# DAC.net
KiCad netlist of a schematic drawn in Altium Designer
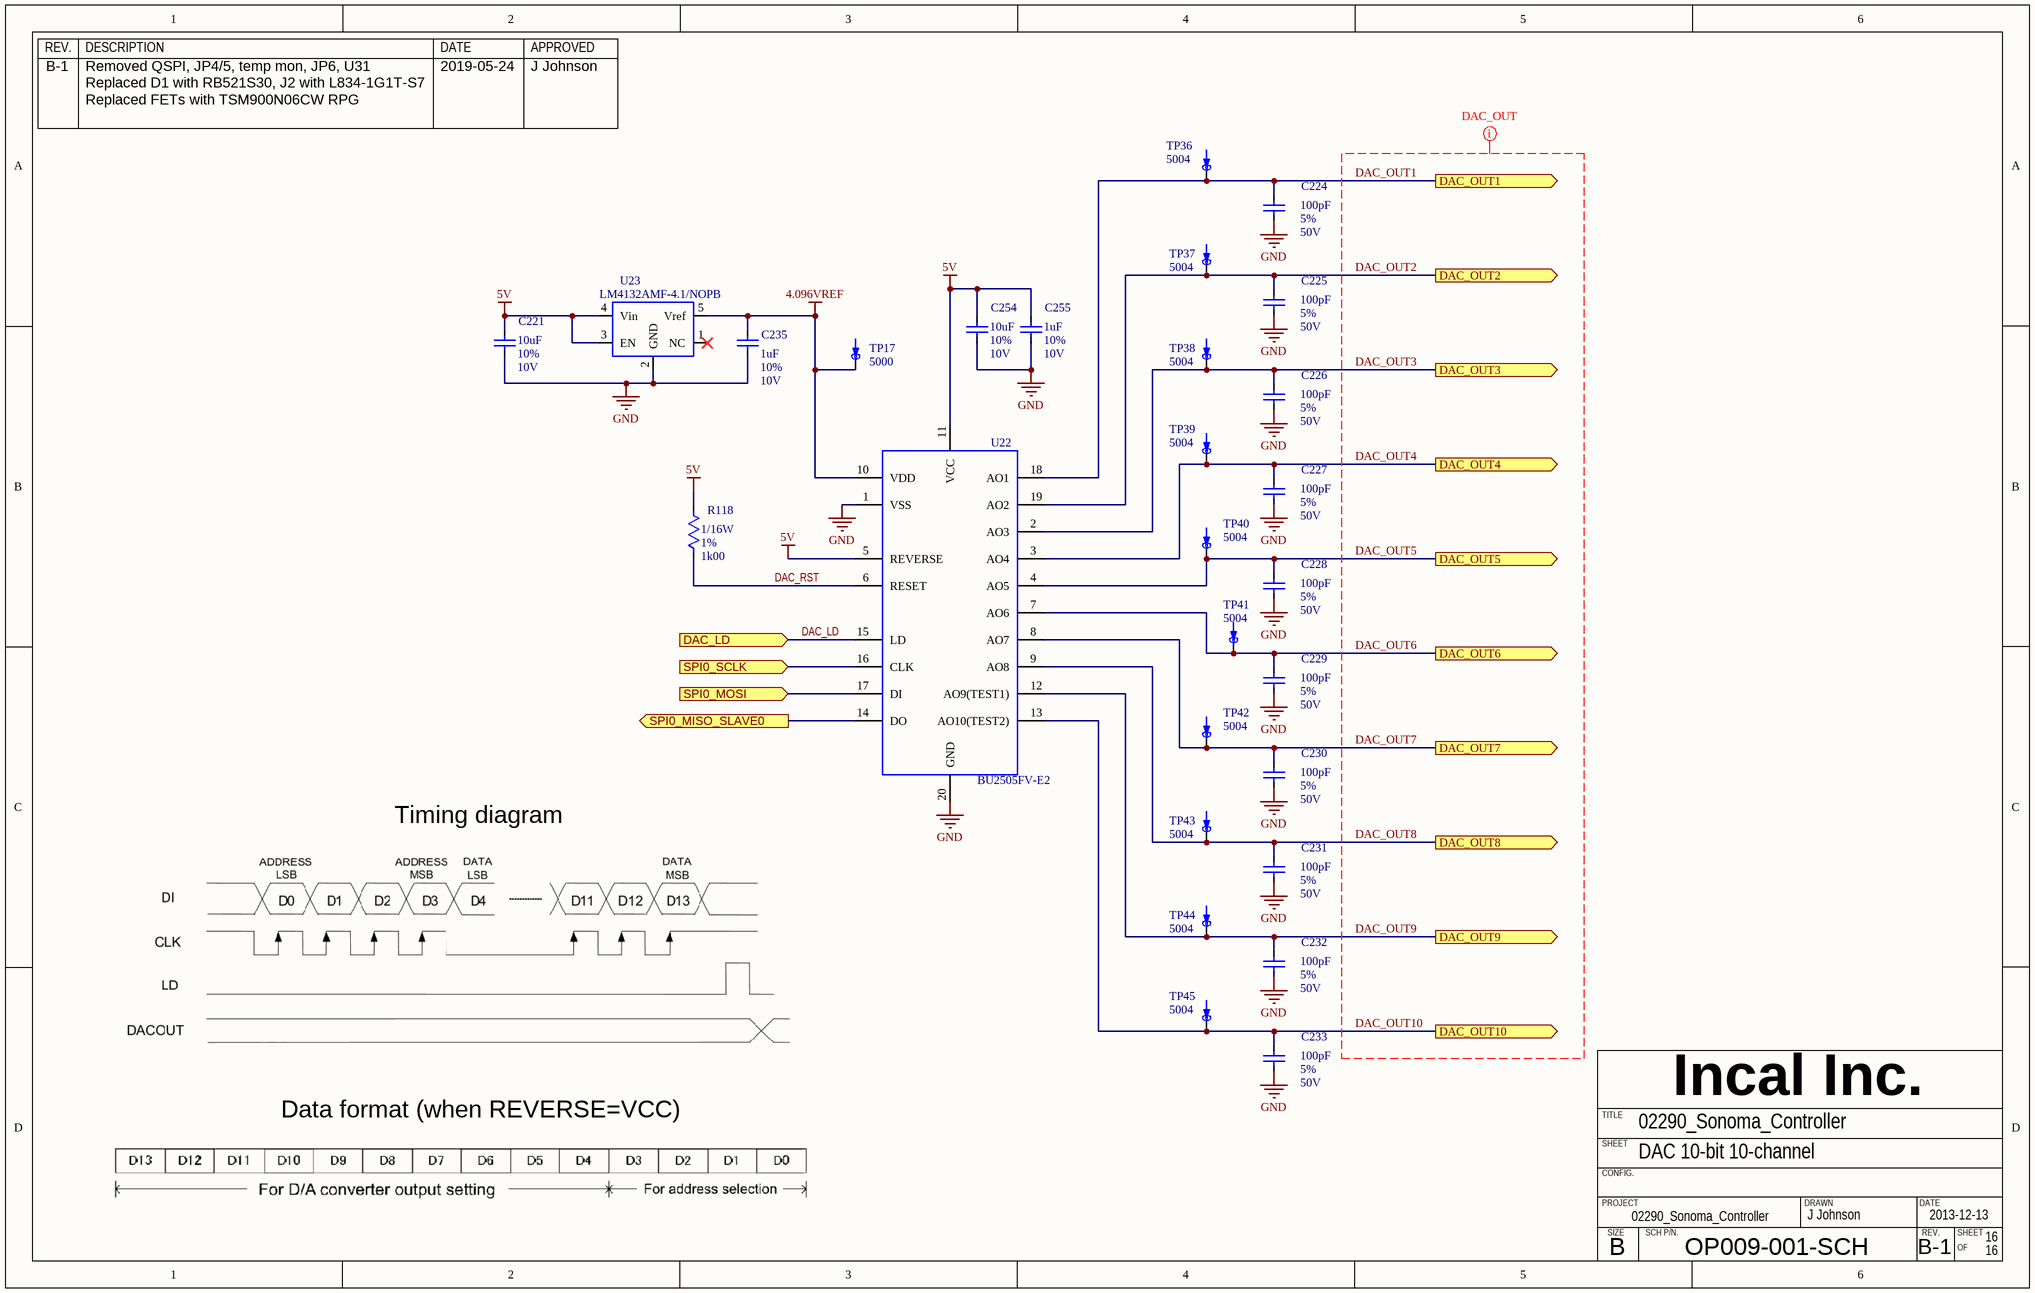
[diagram p0: DAC.SchDoc]

(export (version "E")
  (design (tool "Eeschema 10.0.6"))
  (components
    (comp (ref "C221")
      (value "10uF")
      (footprint "CAPC1608X38N")
      (description "Capacitor ceramic, X5R, 10uF, 10V, 10%, -55 to +85 C, EIA0603")
      (fields
        (field (name "TOLERANCE") "10%")
        (field (name "VOLTAGE") "10V")
        (field (name "Comment") "CAPACITOR_NP_TYPE1")
      )
      (libsource (lib "parts") (part "CAPACITOR_NP_TYPE1"))
    )
    (comp (ref "C224")
      (value "100pF")
      (footprint "CAPC1005X33N")
      (description "Capacitor ceramic, C0G (NP0), 100pF, 50V, 5%, -55 to +125 C, EIA0402")
      (fields
        (field (name "TOLERANCE") "5%")
        (field (name "VOLTAGE") "50V")
        (field (name "Comment") "CAPACITOR_NP_TYPE1")
      )
      (libsource (lib "parts") (part "CAPACITOR_NP_TYPE1"))
    )
    (comp (ref "C225")
      (value "100pF")
      (footprint "CAPC1005X33N")
      (description "Capacitor ceramic, C0G (NP0), 100pF, 50V, 5%, -55 to +125 C, EIA0402")
      (fields
        (field (name "TOLERANCE") "5%")
        (field (name "VOLTAGE") "50V")
        (field (name "Comment") "CAPACITOR_NP_TYPE1")
      )
      (libsource (lib "parts") (part "CAPACITOR_NP_TYPE1"))
    )
    (comp (ref "C226")
      (value "100pF")
      (footprint "CAPC1005X33N")
      (description "Capacitor ceramic, C0G (NP0), 100pF, 50V, 5%, -55 to +125 C, EIA0402")
      (fields
        (field (name "TOLERANCE") "5%")
        (field (name "VOLTAGE") "50V")
        (field (name "Comment") "CAPACITOR_NP_TYPE1")
      )
      (libsource (lib "parts") (part "CAPACITOR_NP_TYPE1"))
    )
    (comp (ref "C227")
      (value "100pF")
      (footprint "CAPC1005X33N")
      (description "Capacitor ceramic, C0G (NP0), 100pF, 50V, 5%, -55 to +125 C, EIA0402")
      (fields
        (field (name "TOLERANCE") "5%")
        (field (name "VOLTAGE") "50V")
        (field (name "Comment") "CAPACITOR_NP_TYPE1")
      )
      (libsource (lib "parts") (part "CAPACITOR_NP_TYPE1"))
    )
    (comp (ref "C228")
      (value "100pF")
      (footprint "CAPC1005X33N")
      (description "Capacitor ceramic, C0G (NP0), 100pF, 50V, 5%, -55 to +125 C, EIA0402")
      (fields
        (field (name "TOLERANCE") "5%")
        (field (name "VOLTAGE") "50V")
        (field (name "Comment") "CAPACITOR_NP_TYPE1")
      )
      (libsource (lib "parts") (part "CAPACITOR_NP_TYPE1"))
    )
    (comp (ref "C229")
      (value "100pF")
      (footprint "CAPC1005X33N")
      (description "Capacitor ceramic, C0G (NP0), 100pF, 50V, 5%, -55 to +125 C, EIA0402")
      (fields
        (field (name "TOLERANCE") "5%")
        (field (name "VOLTAGE") "50V")
        (field (name "Comment") "CAPACITOR_NP_TYPE1")
      )
      (libsource (lib "parts") (part "CAPACITOR_NP_TYPE1"))
    )
    (comp (ref "C230")
      (value "100pF")
      (footprint "CAPC1005X33N")
      (description "Capacitor ceramic, C0G (NP0), 100pF, 50V, 5%, -55 to +125 C, EIA0402")
      (fields
        (field (name "TOLERANCE") "5%")
        (field (name "VOLTAGE") "50V")
        (field (name "Comment") "CAPACITOR_NP_TYPE1")
      )
      (libsource (lib "parts") (part "CAPACITOR_NP_TYPE1"))
    )
    (comp (ref "C231")
      (value "100pF")
      (footprint "CAPC1005X33N")
      (description "Capacitor ceramic, C0G (NP0), 100pF, 50V, 5%, -55 to +125 C, EIA0402")
      (fields
        (field (name "TOLERANCE") "5%")
        (field (name "VOLTAGE") "50V")
        (field (name "Comment") "CAPACITOR_NP_TYPE1")
      )
      (libsource (lib "parts") (part "CAPACITOR_NP_TYPE1"))
    )
    (comp (ref "C232")
      (value "100pF")
      (footprint "CAPC1005X33N")
      (description "Capacitor ceramic, C0G (NP0), 100pF, 50V, 5%, -55 to +125 C, EIA0402")
      (fields
        (field (name "TOLERANCE") "5%")
        (field (name "VOLTAGE") "50V")
        (field (name "Comment") "CAPACITOR_NP_TYPE1")
      )
      (libsource (lib "parts") (part "CAPACITOR_NP_TYPE1"))
    )
    (comp (ref "C233")
      (value "100pF")
      (footprint "CAPC1005X33N")
      (description "Capacitor ceramic, C0G (NP0), 100pF, 50V, 5%, -55 to +125 C, EIA0402")
      (fields
        (field (name "TOLERANCE") "5%")
        (field (name "VOLTAGE") "50V")
        (field (name "Comment") "CAPACITOR_NP_TYPE1")
      )
      (libsource (lib "parts") (part "CAPACITOR_NP_TYPE1"))
    )
    (comp (ref "C235")
      (value "1uF")
      (footprint "CAPC1005X33N")
      (description "Capacitor ceramic, X5R, 1uF, 10V, 10%, -55 to +85 C, EIA0402")
      (fields
        (field (name "TOLERANCE") "10%")
        (field (name "VOLTAGE") "10V")
        (field (name "Comment") "CAPACITOR_NP_TYPE1")
      )
      (libsource (lib "parts") (part "CAPACITOR_NP_TYPE1"))
    )
    (comp (ref "C254")
      (value "10uF")
      (footprint "CAPC1608X38N")
      (description "Capacitor ceramic, X5R, 10uF, 10V, 10%, -55 to +85 C, EIA0603")
      (fields
        (field (name "TOLERANCE") "10%")
        (field (name "VOLTAGE") "10V")
        (field (name "Comment") "CAPACITOR_NP_TYPE1")
      )
      (libsource (lib "parts") (part "CAPACITOR_NP_TYPE1"))
    )
    (comp (ref "C255")
      (value "1uF")
      (footprint "CAPC1005X33N")
      (description "Capacitor ceramic, X5R, 1uF, 10V, 10%, -55 to +85 C, EIA0402")
      (fields
        (field (name "TOLERANCE") "10%")
        (field (name "VOLTAGE") "10V")
        (field (name "Comment") "CAPACITOR_NP_TYPE1")
      )
      (libsource (lib "parts") (part "CAPACITOR_NP_TYPE1"))
    )
    (comp (ref "R118")
      (value "1k00")
      (footprint "RESC1005X33N")
      (description "Resistor, 1k00, 1/16W, 1%, -55 to +155 C, EIA0402")
      (fields (field (name "VOLTAGE") "50V") (field (name "POWER") "1/16W") (field (name "TOLERANCE") "1%"))
      (libsource (lib "parts") (part "RESISTOR_TYPE1"))
    )
    (comp (ref "TP17")
      (value "5000")
      (footprint "KEY_5000")
      (description "Test point bead, red, Keystone Electronics, Thru-hole,")
      (fields (field (name "POWER") "Pow") (field (name "VOLTAGE") "Vol"))
      (libsource (lib "parts") (part "TEST_POINT_TYPE4"))
    )
    (comp (ref "TP36")
      (value "5004")
      (footprint "KEY_5004")
      (description "Test point bead, yellow, Keystone Electronics, Thru-hole,")
      (fields (field (name "POWER") "Pow") (field (name "VOLTAGE") "Vol"))
      (libsource (lib "parts") (part "TEST_POINT_TYPE4"))
    )
    (comp (ref "TP37")
      (value "5004")
      (footprint "KEY_5004")
      (description "Test point bead, yellow, Keystone Electronics, Thru-hole,")
      (fields (field (name "POWER") "Pow") (field (name "VOLTAGE") "Vol"))
      (libsource (lib "parts") (part "TEST_POINT_TYPE4"))
    )
    (comp (ref "TP38")
      (value "5004")
      (footprint "KEY_5004")
      (description "Test point bead, yellow, Keystone Electronics, Thru-hole,")
      (fields (field (name "POWER") "Pow") (field (name "VOLTAGE") "Vol"))
      (libsource (lib "parts") (part "TEST_POINT_TYPE4"))
    )
    (comp (ref "TP39")
      (value "5004")
      (footprint "KEY_5004")
      (description "Test point bead, yellow, Keystone Electronics, Thru-hole,")
      (fields (field (name "POWER") "Pow") (field (name "VOLTAGE") "Vol"))
      (libsource (lib "parts") (part "TEST_POINT_TYPE4"))
    )
    (comp (ref "TP40")
      (value "5004")
      (footprint "KEY_5004")
      (description "Test point bead, yellow, Keystone Electronics, Thru-hole,")
      (fields (field (name "POWER") "Pow") (field (name "VOLTAGE") "Vol"))
      (libsource (lib "parts") (part "TEST_POINT_TYPE4"))
    )
    (comp (ref "TP41")
      (value "5004")
      (footprint "KEY_5004")
      (description "Test point bead, yellow, Keystone Electronics, Thru-hole,")
      (fields (field (name "POWER") "Pow") (field (name "VOLTAGE") "Vol"))
      (libsource (lib "parts") (part "TEST_POINT_TYPE4"))
    )
    (comp (ref "TP42")
      (value "5004")
      (footprint "KEY_5004")
      (description "Test point bead, yellow, Keystone Electronics, Thru-hole,")
      (fields (field (name "POWER") "Pow") (field (name "VOLTAGE") "Vol"))
      (libsource (lib "parts") (part "TEST_POINT_TYPE4"))
    )
    (comp (ref "TP43")
      (value "5004")
      (footprint "KEY_5004")
      (description "Test point bead, yellow, Keystone Electronics, Thru-hole,")
      (fields (field (name "POWER") "Pow") (field (name "VOLTAGE") "Vol"))
      (libsource (lib "parts") (part "TEST_POINT_TYPE4"))
    )
    (comp (ref "TP44")
      (value "5004")
      (footprint "KEY_5004")
      (description "Test point bead, yellow, Keystone Electronics, Thru-hole,")
      (fields (field (name "POWER") "Pow") (field (name "VOLTAGE") "Vol"))
      (libsource (lib "parts") (part "TEST_POINT_TYPE4"))
    )
    (comp (ref "TP45")
      (value "5004")
      (footprint "KEY_5004")
      (description "Test point bead, yellow, Keystone Electronics, Thru-hole,")
      (fields (field (name "POWER") "Pow") (field (name "VOLTAGE") "Vol"))
      (libsource (lib "parts") (part "TEST_POINT_TYPE4"))
    )
    (comp (ref "U22")
      (value "BU2505FV-E2")
      (footprint "SSOP65P440X650X115-20N")
      (description "DAC 10 bit, High precision, 10 channel, 4.5 to 5.5V, -30 to +85C")
      (libsource (lib "parts") (part "BU2505FV-E2"))
    )
    (comp (ref "U23")
      (value "LM4132")
      (footprint "SOT65P280X145-5AN")
      (description "Reference 4.096V low dropout, 20mA, 10ppm, 0.05%")
      (fields
        (field (name "POWER") "Pow")
        (field (name "TOLERANCE") "±0.05%")
        (field (name "MFG PART NUMBER 1") "LM4132AMF-4.1/NOPB")
      )
      (libsource (lib "parts") (part "LM4132"))
    )
  )
  (nets
    (net (code "1") (name "/DAC_LD") (class "Default")
      (node (ref "U22") (pin "15") (pinfunction "LD_15") (pintype "passive"))
    )
    (net (code "2") (name "/DAC_OUT1") (class "Default")
      (node (ref "C224") (pin "1") (pinfunction "1_1") (pintype "passive"))
      (node (ref "TP36") (pin "1") (pinfunction "1_1") (pintype "passive"))
      (node (ref "U22") (pin "18") (pinfunction "AO1_18") (pintype "passive"))
    )
    (net (code "3") (name "/DAC_OUT2") (class "Default")
      (node (ref "C225") (pin "1") (pinfunction "1_1") (pintype "passive"))
      (node (ref "TP37") (pin "1") (pinfunction "1_1") (pintype "passive"))
      (node (ref "U22") (pin "19") (pinfunction "AO2_19") (pintype "passive"))
    )
    (net (code "4") (name "/DAC_OUT3") (class "Default")
      (node (ref "C226") (pin "1") (pinfunction "1_1") (pintype "passive"))
      (node (ref "TP38") (pin "1") (pinfunction "1_1") (pintype "passive"))
      (node (ref "U22") (pin "2") (pinfunction "AO3_2") (pintype "passive"))
    )
    (net (code "5") (name "/DAC_OUT4") (class "Default")
      (node (ref "C227") (pin "1") (pinfunction "1_1") (pintype "passive"))
      (node (ref "TP39") (pin "1") (pinfunction "1_1") (pintype "passive"))
      (node (ref "U22") (pin "3") (pinfunction "AO4_3") (pintype "passive"))
    )
    (net (code "6") (name "/DAC_OUT5") (class "Default")
      (node (ref "C228") (pin "1") (pinfunction "1_1") (pintype "passive"))
      (node (ref "TP40") (pin "1") (pinfunction "1_1") (pintype "passive"))
      (node (ref "U22") (pin "4") (pinfunction "AO5_4") (pintype "passive"))
    )
    (net (code "7") (name "/DAC_OUT6") (class "Default")
      (node (ref "C229") (pin "1") (pinfunction "1_1") (pintype "passive"))
      (node (ref "TP41") (pin "1") (pinfunction "1_1") (pintype "passive"))
      (node (ref "U22") (pin "7") (pinfunction "AO6_7") (pintype "passive"))
    )
    (net (code "8") (name "/DAC_OUT7") (class "Default")
      (node (ref "C230") (pin "1") (pinfunction "1_1") (pintype "passive"))
      (node (ref "TP42") (pin "1") (pinfunction "1_1") (pintype "passive"))
      (node (ref "U22") (pin "8") (pinfunction "AO7_8") (pintype "passive"))
    )
    (net (code "9") (name "/DAC_OUT8") (class "Default")
      (node (ref "C231") (pin "1") (pinfunction "1_1") (pintype "passive"))
      (node (ref "TP43") (pin "1") (pinfunction "1_1") (pintype "passive"))
      (node (ref "U22") (pin "9") (pinfunction "AO8_9") (pintype "passive"))
    )
    (net (code "10") (name "/DAC_OUT9") (class "Default")
      (node (ref "C232") (pin "1") (pinfunction "1_1") (pintype "passive"))
      (node (ref "TP44") (pin "1") (pinfunction "1_1") (pintype "passive"))
      (node (ref "U22") (pin "12") (pinfunction "AO9(TEST1)_12") (pintype "passive"))
    )
    (net (code "11") (name "/DAC_OUT10") (class "Default")
      (node (ref "C233") (pin "1") (pinfunction "1_1") (pintype "passive"))
      (node (ref "TP45") (pin "1") (pinfunction "1_1") (pintype "passive"))
      (node (ref "U22") (pin "13") (pinfunction "AO10(TEST2)_13") (pintype "passive"))
    )
    (net (code "12") (name "/DAC_RST") (class "Default")
      (node (ref "R118") (pin "1") (pinfunction "1_1") (pintype "passive"))
      (node (ref "U22") (pin "6") (pinfunction "RESET_6") (pintype "passive"))
    )
    (net (code "13") (name "/SPI0_MISO_SLAVE0") (class "Default")
      (node (ref "U22") (pin "14") (pinfunction "DO_14") (pintype "passive"))
    )
    (net (code "14") (name "/SPI0_MOSI") (class "Default")
      (node (ref "U22") (pin "17") (pinfunction "DI_17") (pintype "passive"))
    )
    (net (code "15") (name "/SPI0_SCLK") (class "Default")
      (node (ref "U22") (pin "16") (pinfunction "CLK_16") (pintype "passive"))
    )
    (net (code "16") (name "4.096VREF") (class "Default")
      (node (ref "C235") (pin "1") (pinfunction "1_1") (pintype "passive"))
      (node (ref "TP17") (pin "1") (pinfunction "1_1") (pintype "passive"))
      (node (ref "U22") (pin "10") (pinfunction "VDD_10") (pintype "passive"))
      (node (ref "U23") (pin "5") (pinfunction "Vref_5") (pintype "power_in"))
    )
    (net (code "17") (name "5V") (class "Default")
      (node (ref "C221") (pin "1") (pinfunction "1_1") (pintype "passive"))
      (node (ref "C254") (pin "1") (pinfunction "1_1") (pintype "passive"))
      (node (ref "C255") (pin "1") (pinfunction "1_1") (pintype "passive"))
      (node (ref "R118") (pin "2") (pinfunction "2_2") (pintype "passive"))
      (node (ref "U22") (pin "11") (pinfunction "VCC_11") (pintype "passive"))
      (node (ref "U22") (pin "5") (pinfunction "REVERSE_5") (pintype "passive"))
      (node (ref "U23") (pin "3") (pinfunction "EN_3") (pintype "passive"))
      (node (ref "U23") (pin "4") (pinfunction "Vin_4") (pintype "power_in"))
    )
    (net (code "18") (name "GND") (class "Default")
      (node (ref "C221") (pin "2") (pinfunction "2_2") (pintype "passive"))
      (node (ref "C224") (pin "2") (pinfunction "2_2") (pintype "passive"))
      (node (ref "C225") (pin "2") (pinfunction "2_2") (pintype "passive"))
      (node (ref "C226") (pin "2") (pinfunction "2_2") (pintype "passive"))
      (node (ref "C227") (pin "2") (pinfunction "2_2") (pintype "passive"))
      (node (ref "C228") (pin "2") (pinfunction "2_2") (pintype "passive"))
      (node (ref "C229") (pin "2") (pinfunction "2_2") (pintype "passive"))
      (node (ref "C230") (pin "2") (pinfunction "2_2") (pintype "passive"))
      (node (ref "C231") (pin "2") (pinfunction "2_2") (pintype "passive"))
      (node (ref "C232") (pin "2") (pinfunction "2_2") (pintype "passive"))
      (node (ref "C233") (pin "2") (pinfunction "2_2") (pintype "passive"))
      (node (ref "C235") (pin "2") (pinfunction "2_2") (pintype "passive"))
      (node (ref "C254") (pin "2") (pinfunction "2_2") (pintype "passive"))
      (node (ref "C255") (pin "2") (pinfunction "2_2") (pintype "passive"))
      (node (ref "U22") (pin "1") (pinfunction "VSS_1") (pintype "passive"))
      (node (ref "U22") (pin "20") (pinfunction "GND_20") (pintype "passive"))
      (node (ref "U23") (pin "2") (pinfunction "GND_2") (pintype "power_in"))
    )
    (net (code "19") (name "unconnected-(U23-NC-Pad1)") (class "Default")
      (node (ref "U23") (pin "1") (pinfunction "NC_1") (pintype "passive+no_connect"))
    )
  )
)
